# 04-AD9546-Main.net
KiCad netlist of a schematic drawn in Altium Designer
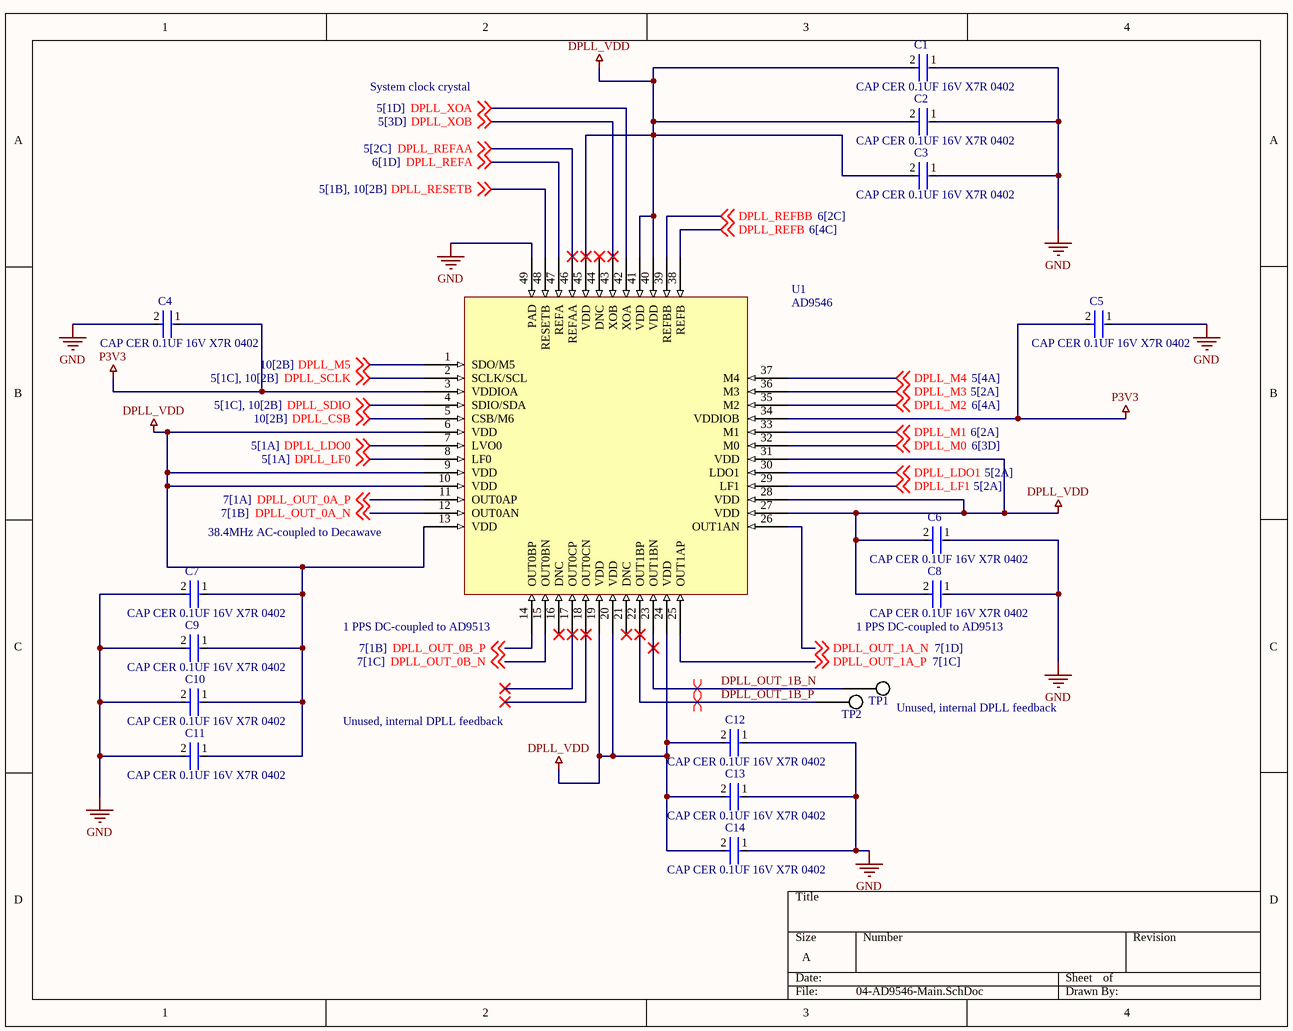
[diagram p0: 04-AD9546-Main.SchDoc]

(export (version "E")
  (design (tool "Eeschema 10.0.6"))
  (components
    (comp (ref "C1")
      (value "GRM155R71C104KA88D")
      (footprint "FP-GRM15-MFG")
      (description "CAP CER 0.1UF 16V X7R 0402")
      (fields
        (field (name "TOLERANCE") "10%")
        (field (name "OCTOPART") "https://octopart.com/grm155r71c104ka88d-murata-196880")
        (field (name "DIGIKEY DESCRIPTION") "CAP CER 0.1UF 16V X7R 0402")
      )
      (libsource (lib "Altium Content Vault") (part "236180d848d6139a670b325ea6854c9"))
    )
    (comp (ref "C2")
      (value "GRM155R71C104KA88D")
      (footprint "FP-GRM15-MFG")
      (description "CAP CER 0.1UF 16V X7R 0402")
      (fields
        (field (name "TOLERANCE") "10%")
        (field (name "OCTOPART") "https://octopart.com/grm155r71c104ka88d-murata-196880")
        (field (name "DIGIKEY DESCRIPTION") "CAP CER 0.1UF 16V X7R 0402")
      )
      (libsource (lib "Altium Content Vault") (part "236180d848d6139a670b325ea6854c9"))
    )
    (comp (ref "C3")
      (value "GRM155R71C104KA88D")
      (footprint "FP-GRM15-MFG")
      (description "CAP CER 0.1UF 16V X7R 0402")
      (fields
        (field (name "TOLERANCE") "10%")
        (field (name "OCTOPART") "https://octopart.com/grm155r71c104ka88d-murata-196880")
        (field (name "DIGIKEY DESCRIPTION") "CAP CER 0.1UF 16V X7R 0402")
      )
      (libsource (lib "Altium Content Vault") (part "236180d848d6139a670b325ea6854c9"))
    )
    (comp (ref "C4")
      (value "GRM155R71C104KA88D")
      (footprint "FP-GRM15-MFG")
      (description "CAP CER 0.1UF 16V X7R 0402")
      (fields
        (field (name "TOLERANCE") "10%")
        (field (name "OCTOPART") "https://octopart.com/grm155r71c104ka88d-murata-196880")
        (field (name "DIGIKEY DESCRIPTION") "CAP CER 0.1UF 16V X7R 0402")
      )
      (libsource (lib "Altium Content Vault") (part "236180d848d6139a670b325ea6854c9"))
    )
    (comp (ref "C5")
      (value "GRM155R71C104KA88D")
      (footprint "FP-GRM15-MFG")
      (description "CAP CER 0.1UF 16V X7R 0402")
      (fields
        (field (name "TOLERANCE") "10%")
        (field (name "OCTOPART") "https://octopart.com/grm155r71c104ka88d-murata-196880")
        (field (name "DIGIKEY DESCRIPTION") "CAP CER 0.1UF 16V X7R 0402")
      )
      (libsource (lib "Altium Content Vault") (part "236180d848d6139a670b325ea6854c9"))
    )
    (comp (ref "C6")
      (value "GRM155R71C104KA88D")
      (footprint "FP-GRM15-MFG")
      (description "CAP CER 0.1UF 16V X7R 0402")
      (fields
        (field (name "TOLERANCE") "10%")
        (field (name "OCTOPART") "https://octopart.com/grm155r71c104ka88d-murata-196880")
        (field (name "DIGIKEY DESCRIPTION") "CAP CER 0.1UF 16V X7R 0402")
      )
      (libsource (lib "Altium Content Vault") (part "236180d848d6139a670b325ea6854c9"))
    )
    (comp (ref "C7")
      (value "GRM155R71C104KA88D")
      (footprint "FP-GRM15-MFG")
      (description "CAP CER 0.1UF 16V X7R 0402")
      (fields
        (field (name "TOLERANCE") "10%")
        (field (name "OCTOPART") "https://octopart.com/grm155r71c104ka88d-murata-196880")
        (field (name "DIGIKEY DESCRIPTION") "CAP CER 0.1UF 16V X7R 0402")
      )
      (libsource (lib "Altium Content Vault") (part "236180d848d6139a670b325ea6854c9"))
    )
    (comp (ref "C8")
      (value "GRM155R71C104KA88D")
      (footprint "FP-GRM15-MFG")
      (description "CAP CER 0.1UF 16V X7R 0402")
      (fields
        (field (name "TOLERANCE") "10%")
        (field (name "OCTOPART") "https://octopart.com/grm155r71c104ka88d-murata-196880")
        (field (name "DIGIKEY DESCRIPTION") "CAP CER 0.1UF 16V X7R 0402")
      )
      (libsource (lib "Altium Content Vault") (part "236180d848d6139a670b325ea6854c9"))
    )
    (comp (ref "C9")
      (value "GRM155R71C104KA88D")
      (footprint "FP-GRM15-MFG")
      (description "CAP CER 0.1UF 16V X7R 0402")
      (fields
        (field (name "TOLERANCE") "10%")
        (field (name "OCTOPART") "https://octopart.com/grm155r71c104ka88d-murata-196880")
        (field (name "DIGIKEY DESCRIPTION") "CAP CER 0.1UF 16V X7R 0402")
      )
      (libsource (lib "Altium Content Vault") (part "236180d848d6139a670b325ea6854c9"))
    )
    (comp (ref "C10")
      (value "GRM155R71C104KA88D")
      (footprint "FP-GRM15-MFG")
      (description "CAP CER 0.1UF 16V X7R 0402")
      (fields
        (field (name "TOLERANCE") "10%")
        (field (name "OCTOPART") "https://octopart.com/grm155r71c104ka88d-murata-196880")
        (field (name "DIGIKEY DESCRIPTION") "CAP CER 0.1UF 16V X7R 0402")
      )
      (libsource (lib "Altium Content Vault") (part "236180d848d6139a670b325ea6854c9"))
    )
    (comp (ref "C11")
      (value "GRM155R71C104KA88D")
      (footprint "FP-GRM15-MFG")
      (description "CAP CER 0.1UF 16V X7R 0402")
      (fields
        (field (name "TOLERANCE") "10%")
        (field (name "OCTOPART") "https://octopart.com/grm155r71c104ka88d-murata-196880")
        (field (name "DIGIKEY DESCRIPTION") "CAP CER 0.1UF 16V X7R 0402")
      )
      (libsource (lib "Altium Content Vault") (part "236180d848d6139a670b325ea6854c9"))
    )
    (comp (ref "C12")
      (value "GRM155R71C104KA88D")
      (footprint "FP-GRM15-MFG")
      (description "CAP CER 0.1UF 16V X7R 0402")
      (fields
        (field (name "TOLERANCE") "10%")
        (field (name "OCTOPART") "https://octopart.com/grm155r71c104ka88d-murata-196880")
        (field (name "DIGIKEY DESCRIPTION") "CAP CER 0.1UF 16V X7R 0402")
      )
      (libsource (lib "Altium Content Vault") (part "236180d848d6139a670b325ea6854c9"))
    )
    (comp (ref "C13")
      (value "GRM155R71C104KA88D")
      (footprint "FP-GRM15-MFG")
      (description "CAP CER 0.1UF 16V X7R 0402")
      (fields
        (field (name "TOLERANCE") "10%")
        (field (name "OCTOPART") "https://octopart.com/grm155r71c104ka88d-murata-196880")
        (field (name "DIGIKEY DESCRIPTION") "CAP CER 0.1UF 16V X7R 0402")
      )
      (libsource (lib "Altium Content Vault") (part "236180d848d6139a670b325ea6854c9"))
    )
    (comp (ref "C14")
      (value "GRM155R71C104KA88D")
      (footprint "FP-GRM15-MFG")
      (description "CAP CER 0.1UF 16V X7R 0402")
      (fields
        (field (name "TOLERANCE") "10%")
        (field (name "OCTOPART") "https://octopart.com/grm155r71c104ka88d-murata-196880")
        (field (name "DIGIKEY DESCRIPTION") "CAP CER 0.1UF 16V X7R 0402")
      )
      (libsource (lib "Altium Content Vault") (part "236180d848d6139a670b325ea6854c9"))
    )
    (comp (ref "TP1")
      (value "SMT_50DIA")
      (footprint "TP001V_SMT_50DIA")
      (description "TEST POINT, PC, SMT, 0.50MM DIA")
      (libsource (lib "FRL Altium Server") (part "TP_NoColor_001pin_No_BOM"))
    )
    (comp (ref "TP2")
      (value "SMT_50DIA")
      (footprint "TP001V_SMT_50DIA")
      (description "TEST POINT, PC, SMT, 0.50MM DIA")
      (libsource (lib "FRL Altium Server") (part "TP_NoColor_001pin_No_BOM"))
    )
    (comp (ref "U1") (value "AD9546") (footprint "AD9546") (libsource (lib "TimeStick_Lib") (part "AD9546")))
  )
  (nets
    (net (code "1") (name "/DPLL_OUT_1B_N") (class "Default")
      (node (ref "TP1") (pin "1") (pinfunction "1_1") (pintype "passive"))
      (node (ref "U1") (pin "23") (pinfunction "OUT1BN_23") (pintype "input"))
    )
    (net (code "2") (name "/DPLL_OUT_1B_P") (class "Default")
      (node (ref "TP2") (pin "1") (pinfunction "1_1") (pintype "passive"))
      (node (ref "U1") (pin "22") (pinfunction "OUT1BP_22") (pintype "input"))
    )
    (net (code "3") (name "DPLL_CSB") (class "Default")
      (node (ref "U1") (pin "5") (pinfunction "CSB/M6_5") (pintype "input"))
    )
    (net (code "4") (name "DPLL_LDO0") (class "Default")
      (node (ref "U1") (pin "7") (pinfunction "LVO0_7") (pintype "input"))
    )
    (net (code "5") (name "DPLL_LDO1") (class "Default")
      (node (ref "U1") (pin "30") (pinfunction "LDO1_30") (pintype "input"))
    )
    (net (code "6") (name "DPLL_LF0") (class "Default")
      (node (ref "U1") (pin "8") (pinfunction "LF0_8") (pintype "input"))
    )
    (net (code "7") (name "DPLL_LF1") (class "Default")
      (node (ref "U1") (pin "29") (pinfunction "LF1_29") (pintype "input"))
    )
    (net (code "8") (name "DPLL_M0") (class "Default")
      (node (ref "U1") (pin "32") (pinfunction "M0_32") (pintype "input"))
    )
    (net (code "9") (name "DPLL_M1") (class "Default")
      (node (ref "U1") (pin "33") (pinfunction "M1_33") (pintype "input"))
    )
    (net (code "10") (name "DPLL_M2") (class "Default")
      (node (ref "U1") (pin "35") (pinfunction "M2_35") (pintype "input"))
    )
    (net (code "11") (name "DPLL_M3") (class "Default")
      (node (ref "U1") (pin "36") (pinfunction "M3_36") (pintype "input"))
    )
    (net (code "12") (name "DPLL_M4") (class "Default")
      (node (ref "U1") (pin "37") (pinfunction "M4_37") (pintype "input"))
    )
    (net (code "13") (name "DPLL_M5") (class "Default")
      (node (ref "U1") (pin "1") (pinfunction "SDO/M5_1") (pintype "input"))
    )
    (net (code "14") (name "DPLL_OUT_0A_N") (class "Default")
      (node (ref "U1") (pin "12") (pinfunction "OUT0AN_12") (pintype "input"))
    )
    (net (code "15") (name "DPLL_OUT_0A_P") (class "Default")
      (node (ref "U1") (pin "11") (pinfunction "OUT0AP_11") (pintype "input"))
    )
    (net (code "16") (name "DPLL_OUT_0B_N") (class "Default")
      (node (ref "U1") (pin "15") (pinfunction "OUT0BN_15") (pintype "input"))
    )
    (net (code "17") (name "DPLL_OUT_0B_P") (class "Default")
      (node (ref "U1") (pin "14") (pinfunction "OUT0BP_14") (pintype "input"))
    )
    (net (code "18") (name "DPLL_OUT_1A_N") (class "Default")
      (node (ref "U1") (pin "26") (pinfunction "OUT1AN_26") (pintype "input"))
    )
    (net (code "19") (name "DPLL_OUT_1A_P") (class "Default")
      (node (ref "U1") (pin "25") (pinfunction "OUT1AP_25") (pintype "input"))
    )
    (net (code "20") (name "DPLL_REFA") (class "Default")
      (node (ref "U1") (pin "47") (pinfunction "REFA_47") (pintype "input"))
    )
    (net (code "21") (name "DPLL_REFAA") (class "Default")
      (node (ref "U1") (pin "46") (pinfunction "REFAA_46") (pintype "input"))
    )
    (net (code "22") (name "DPLL_REFB") (class "Default")
      (node (ref "U1") (pin "38") (pinfunction "REFB_38") (pintype "input"))
    )
    (net (code "23") (name "DPLL_REFBB") (class "Default")
      (node (ref "U1") (pin "39") (pinfunction "REFBB_39") (pintype "input"))
    )
    (net (code "24") (name "DPLL_RESETB") (class "Default")
      (node (ref "U1") (pin "48") (pinfunction "RESETB_48") (pintype "input"))
    )
    (net (code "25") (name "DPLL_SCLK") (class "Default")
      (node (ref "U1") (pin "2") (pinfunction "SCLK/SCL_2") (pintype "input"))
    )
    (net (code "26") (name "DPLL_SDIO") (class "Default")
      (node (ref "U1") (pin "4") (pinfunction "SDIO/SDA_4") (pintype "input"))
    )
    (net (code "27") (name "DPLL_VDD") (class "Default")
      (node (ref "C1") (pin "2") (pinfunction "2_2") (pintype "passive"))
      (node (ref "C10") (pin "1") (pinfunction "1_1") (pintype "passive"))
      (node (ref "C11") (pin "1") (pinfunction "1_1") (pintype "passive"))
      (node (ref "C12") (pin "2") (pinfunction "2_2") (pintype "passive"))
      (node (ref "C13") (pin "2") (pinfunction "2_2") (pintype "passive"))
      (node (ref "C14") (pin "2") (pinfunction "2_2") (pintype "passive"))
      (node (ref "C2") (pin "2") (pinfunction "2_2") (pintype "passive"))
      (node (ref "C3") (pin "2") (pinfunction "2_2") (pintype "passive"))
      (node (ref "C6") (pin "2") (pinfunction "2_2") (pintype "passive"))
      (node (ref "C7") (pin "1") (pinfunction "1_1") (pintype "passive"))
      (node (ref "C8") (pin "2") (pinfunction "2_2") (pintype "passive"))
      (node (ref "C9") (pin "1") (pinfunction "1_1") (pintype "passive"))
      (node (ref "U1") (pin "10") (pinfunction "VDD_10") (pintype "input"))
      (node (ref "U1") (pin "13") (pinfunction "VDD_13") (pintype "input"))
      (node (ref "U1") (pin "19") (pinfunction "VDD_19") (pintype "input"))
      (node (ref "U1") (pin "20") (pinfunction "VDD_20") (pintype "input"))
      (node (ref "U1") (pin "24") (pinfunction "VDD_24") (pintype "input"))
      (node (ref "U1") (pin "27") (pinfunction "VDD_27") (pintype "input"))
      (node (ref "U1") (pin "28") (pinfunction "VDD_28") (pintype "input"))
      (node (ref "U1") (pin "31") (pinfunction "VDD_31") (pintype "input"))
      (node (ref "U1") (pin "40") (pinfunction "VDD_40") (pintype "input"))
      (node (ref "U1") (pin "41") (pinfunction "VDD_41") (pintype "input"))
      (node (ref "U1") (pin "45") (pinfunction "VDD_45") (pintype "input"))
      (node (ref "U1") (pin "6") (pinfunction "VDD_6") (pintype "input"))
      (node (ref "U1") (pin "9") (pinfunction "VDD_9") (pintype "input"))
    )
    (net (code "28") (name "DPLL_XOA") (class "Default")
      (node (ref "U1") (pin "42") (pinfunction "XOA_42") (pintype "input"))
    )
    (net (code "29") (name "DPLL_XOB") (class "Default")
      (node (ref "U1") (pin "43") (pinfunction "XOB_43") (pintype "input"))
    )
    (net (code "30") (name "GND") (class "Default")
      (node (ref "C1") (pin "1") (pinfunction "1_1") (pintype "passive"))
      (node (ref "C10") (pin "2") (pinfunction "2_2") (pintype "passive"))
      (node (ref "C11") (pin "2") (pinfunction "2_2") (pintype "passive"))
      (node (ref "C12") (pin "1") (pinfunction "1_1") (pintype "passive"))
      (node (ref "C13") (pin "1") (pinfunction "1_1") (pintype "passive"))
      (node (ref "C14") (pin "1") (pinfunction "1_1") (pintype "passive"))
      (node (ref "C2") (pin "1") (pinfunction "1_1") (pintype "passive"))
      (node (ref "C3") (pin "1") (pinfunction "1_1") (pintype "passive"))
      (node (ref "C4") (pin "2") (pinfunction "2_2") (pintype "passive"))
      (node (ref "C5") (pin "1") (pinfunction "1_1") (pintype "passive"))
      (node (ref "C6") (pin "1") (pinfunction "1_1") (pintype "passive"))
      (node (ref "C7") (pin "2") (pinfunction "2_2") (pintype "passive"))
      (node (ref "C8") (pin "1") (pinfunction "1_1") (pintype "passive"))
      (node (ref "C9") (pin "2") (pinfunction "2_2") (pintype "passive"))
      (node (ref "U1") (pin "49") (pinfunction "PAD_49") (pintype "input"))
    )
    (net (code "31") (name "P3V3") (class "Default")
      (node (ref "C4") (pin "1") (pinfunction "1_1") (pintype "passive"))
      (node (ref "C5") (pin "2") (pinfunction "2_2") (pintype "passive"))
      (node (ref "U1") (pin "3") (pinfunction "VDDIOA_3") (pintype "input"))
      (node (ref "U1") (pin "34") (pinfunction "VDDIOB_34") (pintype "input"))
    )
    (net (code "32") (name "unconnected-(U1-DNC-Pad16)") (class "Default")
      (node (ref "U1") (pin "16") (pinfunction "DNC_16") (pintype "input+no_connect"))
    )
    (net (code "33") (name "unconnected-(U1-DNC-Pad21)") (class "Default")
      (node (ref "U1") (pin "21") (pinfunction "DNC_21") (pintype "input+no_connect"))
    )
    (net (code "34") (name "unconnected-(U1-DNC-Pad44)") (class "Default")
      (node (ref "U1") (pin "44") (pinfunction "DNC_44") (pintype "input+no_connect"))
    )
    (net (code "35") (name "unconnected-(U1-OUT0CN-Pad18)") (class "Default")
      (node (ref "U1") (pin "18") (pinfunction "OUT0CN_18") (pintype "input+no_connect"))
    )
    (net (code "36") (name "unconnected-(U1-OUT0CP-Pad17)") (class "Default")
      (node (ref "U1") (pin "17") (pinfunction "OUT0CP_17") (pintype "input+no_connect"))
    )
  )
)
